# board.net
KiCad netlist of a schematic drawn in EAGLE
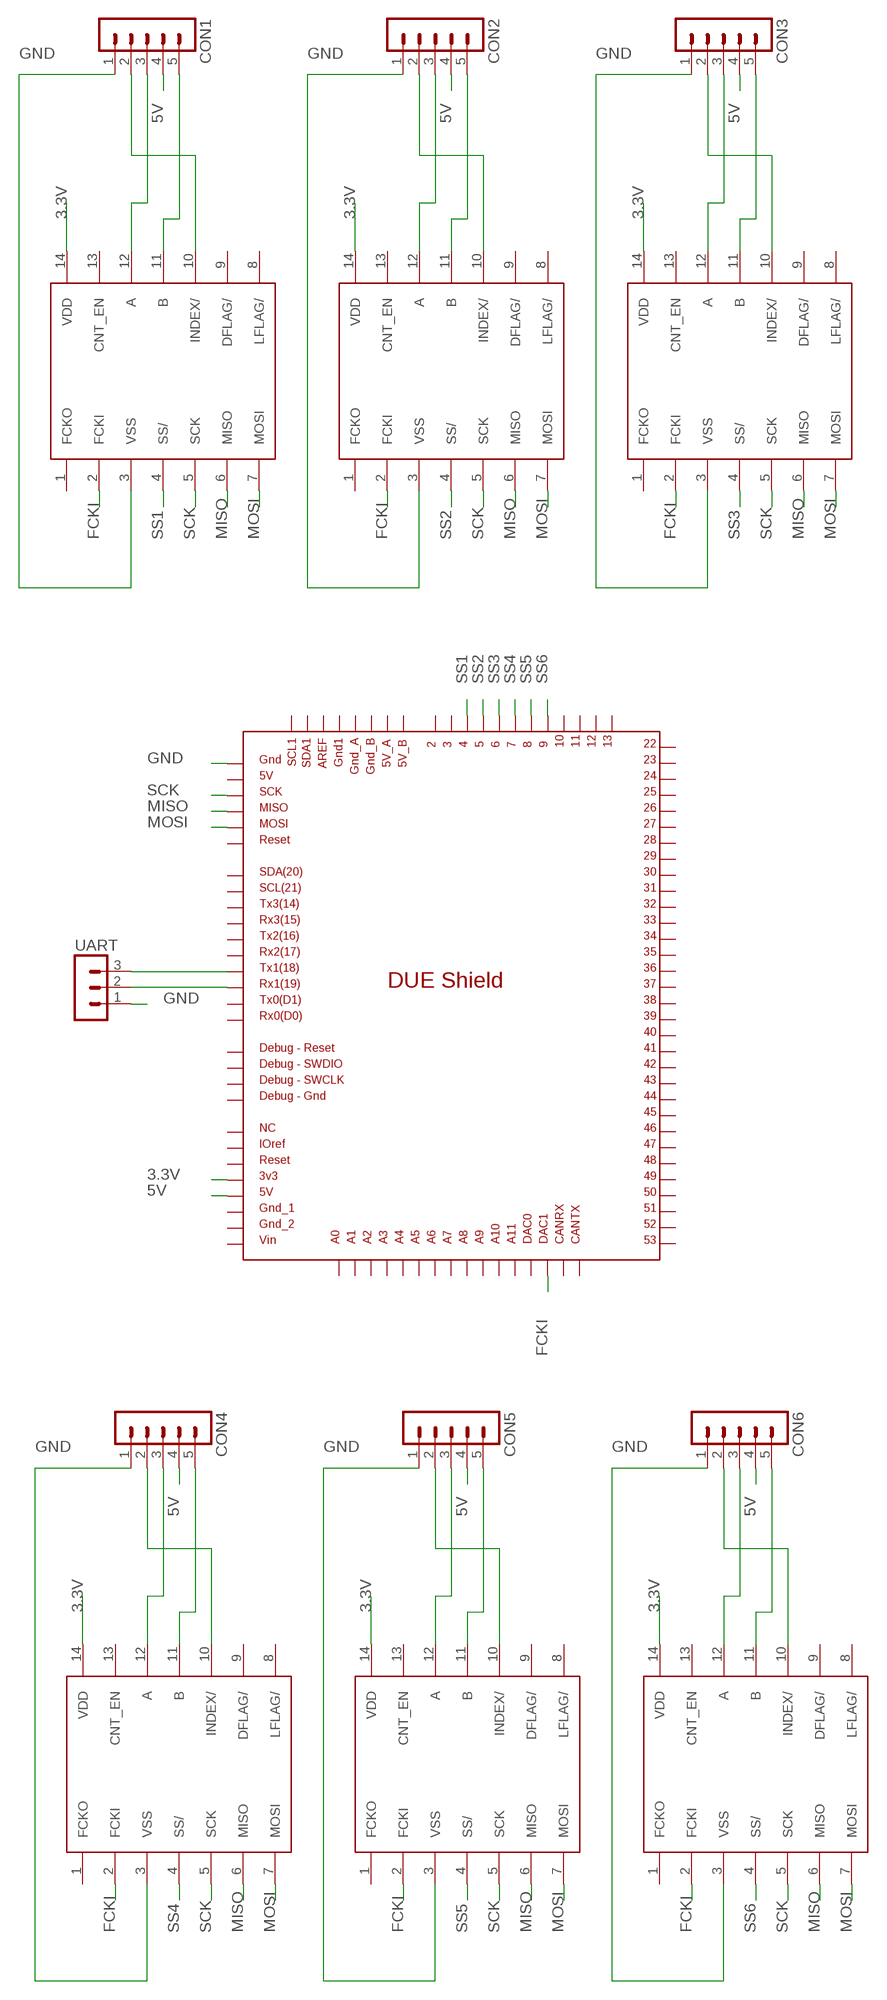
[diagram p0: schematic, sheet 1]

(export (version "E")
  (design (tool "Eeschema 10.0.6"))
  (components
    (comp (ref "CON1")
      (value "MA05-1")
      (footprint "eagle-import:MA05-1")
      (libsource (lib "eagle-import") (part "MA05-1"))
    )
    (comp (ref "CON2")
      (value "MA05-1")
      (footprint "eagle-import:MA05-1")
      (libsource (lib "eagle-import") (part "MA05-1"))
    )
    (comp (ref "CON3")
      (value "MA05-1")
      (footprint "eagle-import:MA05-1")
      (libsource (lib "eagle-import") (part "MA05-1"))
    )
    (comp (ref "CON4")
      (value "MA05-1")
      (footprint "eagle-import:MA05-1")
      (libsource (lib "eagle-import") (part "MA05-1"))
    )
    (comp (ref "CON5")
      (value "MA05-1")
      (footprint "eagle-import:MA05-1")
      (libsource (lib "eagle-import") (part "MA05-1"))
    )
    (comp (ref "CON6")
      (value "MA05-1")
      (footprint "eagle-import:MA05-1")
      (libsource (lib "eagle-import") (part "MA05-1"))
    )
    (comp (ref "IC1")
      (value "LFLS7366R")
      (footprint "eagle-import:SO14")
      (libsource (lib "eagle-import") (part "LFLS7366R"))
    )
    (comp (ref "IC2")
      (value "LFLS7366R")
      (footprint "eagle-import:SO14")
      (libsource (lib "eagle-import") (part "LFLS7366R"))
    )
    (comp (ref "IC3")
      (value "LFLS7366R")
      (footprint "eagle-import:SO14")
      (libsource (lib "eagle-import") (part "LFLS7366R"))
    )
    (comp (ref "IC4")
      (value "LFLS7366R")
      (footprint "eagle-import:SO14")
      (libsource (lib "eagle-import") (part "LFLS7366R"))
    )
    (comp (ref "IC5")
      (value "LFLS7366R")
      (footprint "eagle-import:SO14")
      (libsource (lib "eagle-import") (part "LFLS7366R"))
    )
    (comp (ref "IC6")
      (value "LFLS7366R")
      (footprint "eagle-import:SO14")
      (libsource (lib "eagle-import") (part "LFLS7366R"))
    )
    (comp (ref "U$7")
      (value "DUE(NORMAL)")
      (footprint "eagle-import:DUE(NORMAL)")
      (libsource (lib "eagle-import") (part "DUE(NORMAL)"))
    )
    (comp (ref "UART")
      (value "MA03-1")
      (footprint "eagle-import:MA03-1")
      (libsource (lib "eagle-import") (part "MA03-1"))
    )
  )
  (nets
    (net (code "1") (name "/3.3V") (class "Default")
      (node (ref "IC1") (pin "14") (pinfunction "VDD_14") (pintype "bidirectional"))
      (node (ref "IC2") (pin "14") (pinfunction "VDD_14") (pintype "bidirectional"))
      (node (ref "IC3") (pin "14") (pinfunction "VDD_14") (pintype "bidirectional"))
      (node (ref "IC4") (pin "14") (pinfunction "VDD_14") (pintype "bidirectional"))
      (node (ref "IC5") (pin "14") (pinfunction "VDD_14") (pintype "bidirectional"))
      (node (ref "IC6") (pin "14") (pinfunction "VDD_14") (pintype "bidirectional"))
      (node (ref "U$7") (pin "3V3") (pinfunction "3V3_3V3") (pintype "bidirectional"))
    )
    (net (code "2") (name "/5V") (class "Default")
      (node (ref "CON1") (pin "4") (pinfunction "4_4") (pintype "passive"))
      (node (ref "CON2") (pin "4") (pinfunction "4_4") (pintype "passive"))
      (node (ref "CON3") (pin "4") (pinfunction "4_4") (pintype "passive"))
      (node (ref "CON4") (pin "4") (pinfunction "4_4") (pintype "passive"))
      (node (ref "CON5") (pin "4") (pinfunction "4_4") (pintype "passive"))
      (node (ref "CON6") (pin "4") (pinfunction "4_4") (pintype "passive"))
      (node (ref "U$7") (pin "5V") (pinfunction "5V_5V") (pintype "bidirectional"))
    )
    (net (code "3") (name "/FCKI") (class "Default")
      (node (ref "IC1") (pin "2") (pinfunction "FCKI_2") (pintype "bidirectional"))
      (node (ref "IC2") (pin "2") (pinfunction "FCKI_2") (pintype "bidirectional"))
      (node (ref "IC3") (pin "2") (pinfunction "FCKI_2") (pintype "bidirectional"))
      (node (ref "IC4") (pin "2") (pinfunction "FCKI_2") (pintype "bidirectional"))
      (node (ref "IC5") (pin "2") (pinfunction "FCKI_2") (pintype "bidirectional"))
      (node (ref "IC6") (pin "2") (pinfunction "FCKI_2") (pintype "bidirectional"))
      (node (ref "U$7") (pin "DAC1") (pinfunction "DAC1_DAC1") (pintype "bidirectional"))
    )
    (net (code "4") (name "/GND") (class "Default")
      (node (ref "CON1") (pin "1") (pinfunction "1_1") (pintype "passive"))
      (node (ref "CON2") (pin "1") (pinfunction "1_1") (pintype "passive"))
      (node (ref "CON3") (pin "1") (pinfunction "1_1") (pintype "passive"))
      (node (ref "CON4") (pin "1") (pinfunction "1_1") (pintype "passive"))
      (node (ref "CON5") (pin "1") (pinfunction "1_1") (pintype "passive"))
      (node (ref "CON6") (pin "1") (pinfunction "1_1") (pintype "passive"))
      (node (ref "IC1") (pin "3") (pinfunction "VSS_3") (pintype "bidirectional"))
      (node (ref "IC2") (pin "3") (pinfunction "VSS_3") (pintype "bidirectional"))
      (node (ref "IC3") (pin "3") (pinfunction "VSS_3") (pintype "bidirectional"))
      (node (ref "IC4") (pin "3") (pinfunction "VSS_3") (pintype "bidirectional"))
      (node (ref "IC5") (pin "3") (pinfunction "VSS_3") (pintype "bidirectional"))
      (node (ref "IC6") (pin "3") (pinfunction "VSS_3") (pintype "bidirectional"))
      (node (ref "U$7") (pin "5V_ICSP") (pinfunction "5V_ICSP_5V_ICSP") (pintype "bidirectional"))
      (node (ref "UART") (pin "1") (pinfunction "1_1") (pintype "passive"))
    )
    (net (code "5") (name "/MISO") (class "Default")
      (node (ref "IC1") (pin "6") (pinfunction "MISO_6") (pintype "bidirectional"))
      (node (ref "IC2") (pin "6") (pinfunction "MISO_6") (pintype "bidirectional"))
      (node (ref "IC3") (pin "6") (pinfunction "MISO_6") (pintype "bidirectional"))
      (node (ref "IC4") (pin "6") (pinfunction "MISO_6") (pintype "bidirectional"))
      (node (ref "IC5") (pin "6") (pinfunction "MISO_6") (pintype "bidirectional"))
      (node (ref "IC6") (pin "6") (pinfunction "MISO_6") (pintype "bidirectional"))
      (node (ref "U$7") (pin "MISO_ICSP") (pinfunction "MISO_ICSP_MISO_ICSP") (pintype "bidirectional"))
    )
    (net (code "6") (name "/MOSI") (class "Default")
      (node (ref "IC1") (pin "7") (pinfunction "MOSI_7") (pintype "bidirectional"))
      (node (ref "IC2") (pin "7") (pinfunction "MOSI_7") (pintype "bidirectional"))
      (node (ref "IC3") (pin "7") (pinfunction "MOSI_7") (pintype "bidirectional"))
      (node (ref "IC4") (pin "7") (pinfunction "MOSI_7") (pintype "bidirectional"))
      (node (ref "IC5") (pin "7") (pinfunction "MOSI_7") (pintype "bidirectional"))
      (node (ref "IC6") (pin "7") (pinfunction "MOSI_7") (pintype "bidirectional"))
      (node (ref "U$7") (pin "MOSI_ICSP") (pinfunction "MOSI_ICSP_MOSI_ICSP") (pintype "bidirectional"))
    )
    (net (code "7") (name "/SCK") (class "Default")
      (node (ref "IC1") (pin "5") (pinfunction "SCK_5") (pintype "bidirectional"))
      (node (ref "IC2") (pin "5") (pinfunction "SCK_5") (pintype "bidirectional"))
      (node (ref "IC3") (pin "5") (pinfunction "SCK_5") (pintype "bidirectional"))
      (node (ref "IC4") (pin "5") (pinfunction "SCK_5") (pintype "bidirectional"))
      (node (ref "IC5") (pin "5") (pinfunction "SCK_5") (pintype "bidirectional"))
      (node (ref "IC6") (pin "5") (pinfunction "SCK_5") (pintype "bidirectional"))
      (node (ref "U$7") (pin "SCK_ICSP") (pinfunction "SCK_ICSP_SCK_ICSP") (pintype "bidirectional"))
    )
    (net (code "8") (name "/SS1") (class "Default")
      (node (ref "IC1") (pin "4") (pinfunction "SS/_4") (pintype "bidirectional"))
      (node (ref "U$7") (pin "4") (pinfunction "4_4") (pintype "bidirectional"))
    )
    (net (code "9") (name "/SS2") (class "Default")
      (node (ref "IC2") (pin "4") (pinfunction "SS/_4") (pintype "bidirectional"))
      (node (ref "U$7") (pin "5") (pinfunction "5_5") (pintype "bidirectional"))
    )
    (net (code "10") (name "/SS3") (class "Default")
      (node (ref "IC3") (pin "4") (pinfunction "SS/_4") (pintype "bidirectional"))
      (node (ref "U$7") (pin "6") (pinfunction "6_6") (pintype "bidirectional"))
    )
    (net (code "11") (name "/SS4") (class "Default")
      (node (ref "IC4") (pin "4") (pinfunction "SS/_4") (pintype "bidirectional"))
      (node (ref "U$7") (pin "7") (pinfunction "7_7") (pintype "bidirectional"))
    )
    (net (code "12") (name "/SS5") (class "Default")
      (node (ref "IC5") (pin "4") (pinfunction "SS/_4") (pintype "bidirectional"))
      (node (ref "U$7") (pin "8") (pinfunction "8_8") (pintype "bidirectional"))
    )
    (net (code "13") (name "/SS6") (class "Default")
      (node (ref "IC6") (pin "4") (pinfunction "SS/_4") (pintype "bidirectional"))
      (node (ref "U$7") (pin "9") (pinfunction "9_9") (pintype "bidirectional"))
    )
    (net (code "14") (name "Net-(IC1-A)") (class "Default")
      (node (ref "CON1") (pin "3") (pinfunction "3_3") (pintype "passive"))
      (node (ref "IC1") (pin "12") (pinfunction "A_12") (pintype "bidirectional"))
    )
    (net (code "15") (name "Net-(IC1-B)") (class "Default")
      (node (ref "CON1") (pin "5") (pinfunction "5_5") (pintype "passive"))
      (node (ref "IC1") (pin "11") (pinfunction "B_11") (pintype "bidirectional"))
    )
    (net (code "16") (name "Net-(IC1-INDEX{slash})") (class "Default")
      (node (ref "CON1") (pin "2") (pinfunction "2_2") (pintype "passive"))
      (node (ref "IC1") (pin "10") (pinfunction "INDEX/_10") (pintype "bidirectional"))
    )
    (net (code "17") (name "Net-(IC2-A)") (class "Default")
      (node (ref "CON2") (pin "3") (pinfunction "3_3") (pintype "passive"))
      (node (ref "IC2") (pin "12") (pinfunction "A_12") (pintype "bidirectional"))
    )
    (net (code "18") (name "Net-(IC2-B)") (class "Default")
      (node (ref "CON2") (pin "5") (pinfunction "5_5") (pintype "passive"))
      (node (ref "IC2") (pin "11") (pinfunction "B_11") (pintype "bidirectional"))
    )
    (net (code "19") (name "Net-(IC2-INDEX{slash})") (class "Default")
      (node (ref "CON2") (pin "2") (pinfunction "2_2") (pintype "passive"))
      (node (ref "IC2") (pin "10") (pinfunction "INDEX/_10") (pintype "bidirectional"))
    )
    (net (code "20") (name "Net-(IC3-A)") (class "Default")
      (node (ref "CON3") (pin "3") (pinfunction "3_3") (pintype "passive"))
      (node (ref "IC3") (pin "12") (pinfunction "A_12") (pintype "bidirectional"))
    )
    (net (code "21") (name "Net-(IC3-B)") (class "Default")
      (node (ref "CON3") (pin "5") (pinfunction "5_5") (pintype "passive"))
      (node (ref "IC3") (pin "11") (pinfunction "B_11") (pintype "bidirectional"))
    )
    (net (code "22") (name "Net-(IC3-INDEX{slash})") (class "Default")
      (node (ref "CON3") (pin "2") (pinfunction "2_2") (pintype "passive"))
      (node (ref "IC3") (pin "10") (pinfunction "INDEX/_10") (pintype "bidirectional"))
    )
    (net (code "23") (name "Net-(IC4-A)") (class "Default")
      (node (ref "CON4") (pin "3") (pinfunction "3_3") (pintype "passive"))
      (node (ref "IC4") (pin "12") (pinfunction "A_12") (pintype "bidirectional"))
    )
    (net (code "24") (name "Net-(IC4-B)") (class "Default")
      (node (ref "CON4") (pin "5") (pinfunction "5_5") (pintype "passive"))
      (node (ref "IC4") (pin "11") (pinfunction "B_11") (pintype "bidirectional"))
    )
    (net (code "25") (name "Net-(IC4-INDEX{slash})") (class "Default")
      (node (ref "CON4") (pin "2") (pinfunction "2_2") (pintype "passive"))
      (node (ref "IC4") (pin "10") (pinfunction "INDEX/_10") (pintype "bidirectional"))
    )
    (net (code "26") (name "Net-(IC5-A)") (class "Default")
      (node (ref "CON5") (pin "3") (pinfunction "3_3") (pintype "passive"))
      (node (ref "IC5") (pin "12") (pinfunction "A_12") (pintype "bidirectional"))
    )
    (net (code "27") (name "Net-(IC5-B)") (class "Default")
      (node (ref "CON5") (pin "5") (pinfunction "5_5") (pintype "passive"))
      (node (ref "IC5") (pin "11") (pinfunction "B_11") (pintype "bidirectional"))
    )
    (net (code "28") (name "Net-(IC5-INDEX{slash})") (class "Default")
      (node (ref "CON5") (pin "2") (pinfunction "2_2") (pintype "passive"))
      (node (ref "IC5") (pin "10") (pinfunction "INDEX/_10") (pintype "bidirectional"))
    )
    (net (code "29") (name "Net-(IC6-A)") (class "Default")
      (node (ref "CON6") (pin "3") (pinfunction "3_3") (pintype "passive"))
      (node (ref "IC6") (pin "12") (pinfunction "A_12") (pintype "bidirectional"))
    )
    (net (code "30") (name "Net-(IC6-B)") (class "Default")
      (node (ref "CON6") (pin "5") (pinfunction "5_5") (pintype "passive"))
      (node (ref "IC6") (pin "11") (pinfunction "B_11") (pintype "bidirectional"))
    )
    (net (code "31") (name "Net-(IC6-INDEX{slash})") (class "Default")
      (node (ref "CON6") (pin "2") (pinfunction "2_2") (pintype "passive"))
      (node (ref "IC6") (pin "10") (pinfunction "INDEX/_10") (pintype "bidirectional"))
    )
    (net (code "32") (name "Net-(U$7-PadRX1)") (class "Default")
      (node (ref "U$7") (pin "RX1") (pinfunction "RX1_RX1") (pintype "bidirectional"))
      (node (ref "UART") (pin "2") (pinfunction "2_2") (pintype "passive"))
    )
    (net (code "33") (name "Net-(U$7-PadTX1)") (class "Default")
      (node (ref "U$7") (pin "TX1") (pinfunction "TX1_TX1") (pintype "bidirectional"))
      (node (ref "UART") (pin "3") (pinfunction "3_3") (pintype "passive"))
    )
    (net (code "34") (name "unconnected-(IC1-CNT_EN-Pad13)") (class "Default")
      (node (ref "IC1") (pin "13") (pinfunction "CNT_EN_13") (pintype "bidirectional"))
    )
    (net (code "35") (name "unconnected-(IC1-DFLAG{slash}-Pad9)") (class "Default")
      (node (ref "IC1") (pin "9") (pinfunction "DFLAG/_9") (pintype "bidirectional"))
    )
    (net (code "36") (name "unconnected-(IC1-FCKO-Pad1)") (class "Default")
      (node (ref "IC1") (pin "1") (pinfunction "FCKO_1") (pintype "bidirectional"))
    )
    (net (code "37") (name "unconnected-(IC1-LFLAG{slash}-Pad8)") (class "Default")
      (node (ref "IC1") (pin "8") (pinfunction "LFLAG/_8") (pintype "bidirectional"))
    )
    (net (code "38") (name "unconnected-(IC2-CNT_EN-Pad13)") (class "Default")
      (node (ref "IC2") (pin "13") (pinfunction "CNT_EN_13") (pintype "bidirectional"))
    )
    (net (code "39") (name "unconnected-(IC2-DFLAG{slash}-Pad9)") (class "Default")
      (node (ref "IC2") (pin "9") (pinfunction "DFLAG/_9") (pintype "bidirectional"))
    )
    (net (code "40") (name "unconnected-(IC2-FCKO-Pad1)") (class "Default")
      (node (ref "IC2") (pin "1") (pinfunction "FCKO_1") (pintype "bidirectional"))
    )
    (net (code "41") (name "unconnected-(IC2-LFLAG{slash}-Pad8)") (class "Default")
      (node (ref "IC2") (pin "8") (pinfunction "LFLAG/_8") (pintype "bidirectional"))
    )
    (net (code "42") (name "unconnected-(IC3-CNT_EN-Pad13)") (class "Default")
      (node (ref "IC3") (pin "13") (pinfunction "CNT_EN_13") (pintype "bidirectional"))
    )
    (net (code "43") (name "unconnected-(IC3-DFLAG{slash}-Pad9)") (class "Default")
      (node (ref "IC3") (pin "9") (pinfunction "DFLAG/_9") (pintype "bidirectional"))
    )
    (net (code "44") (name "unconnected-(IC3-FCKO-Pad1)") (class "Default")
      (node (ref "IC3") (pin "1") (pinfunction "FCKO_1") (pintype "bidirectional"))
    )
    (net (code "45") (name "unconnected-(IC3-LFLAG{slash}-Pad8)") (class "Default")
      (node (ref "IC3") (pin "8") (pinfunction "LFLAG/_8") (pintype "bidirectional"))
    )
    (net (code "46") (name "unconnected-(IC4-CNT_EN-Pad13)") (class "Default")
      (node (ref "IC4") (pin "13") (pinfunction "CNT_EN_13") (pintype "bidirectional"))
    )
    (net (code "47") (name "unconnected-(IC4-DFLAG{slash}-Pad9)") (class "Default")
      (node (ref "IC4") (pin "9") (pinfunction "DFLAG/_9") (pintype "bidirectional"))
    )
    (net (code "48") (name "unconnected-(IC4-FCKO-Pad1)") (class "Default")
      (node (ref "IC4") (pin "1") (pinfunction "FCKO_1") (pintype "bidirectional"))
    )
    (net (code "49") (name "unconnected-(IC4-LFLAG{slash}-Pad8)") (class "Default")
      (node (ref "IC4") (pin "8") (pinfunction "LFLAG/_8") (pintype "bidirectional"))
    )
    (net (code "50") (name "unconnected-(IC5-CNT_EN-Pad13)") (class "Default")
      (node (ref "IC5") (pin "13") (pinfunction "CNT_EN_13") (pintype "bidirectional"))
    )
    (net (code "51") (name "unconnected-(IC5-DFLAG{slash}-Pad9)") (class "Default")
      (node (ref "IC5") (pin "9") (pinfunction "DFLAG/_9") (pintype "bidirectional"))
    )
    (net (code "52") (name "unconnected-(IC5-FCKO-Pad1)") (class "Default")
      (node (ref "IC5") (pin "1") (pinfunction "FCKO_1") (pintype "bidirectional"))
    )
    (net (code "53") (name "unconnected-(IC5-LFLAG{slash}-Pad8)") (class "Default")
      (node (ref "IC5") (pin "8") (pinfunction "LFLAG/_8") (pintype "bidirectional"))
    )
    (net (code "54") (name "unconnected-(IC6-CNT_EN-Pad13)") (class "Default")
      (node (ref "IC6") (pin "13") (pinfunction "CNT_EN_13") (pintype "bidirectional"))
    )
    (net (code "55") (name "unconnected-(IC6-DFLAG{slash}-Pad9)") (class "Default")
      (node (ref "IC6") (pin "9") (pinfunction "DFLAG/_9") (pintype "bidirectional"))
    )
    (net (code "56") (name "unconnected-(IC6-FCKO-Pad1)") (class "Default")
      (node (ref "IC6") (pin "1") (pinfunction "FCKO_1") (pintype "bidirectional"))
    )
    (net (code "57") (name "unconnected-(IC6-LFLAG{slash}-Pad8)") (class "Default")
      (node (ref "IC6") (pin "8") (pinfunction "LFLAG/_8") (pintype "bidirectional"))
    )
    (net (code "58") (name "unconnected-(U$7-Pad2)") (class "Default")
      (node (ref "U$7") (pin "2") (pinfunction "2_2") (pintype "bidirectional"))
    )
    (net (code "59") (name "unconnected-(U$7-Pad3)") (class "Default")
      (node (ref "U$7") (pin "3") (pinfunction "3_3") (pintype "bidirectional"))
    )
    (net (code "60") (name "unconnected-(U$7-Pad5V_A)") (class "Default")
      (node (ref "U$7") (pin "5V_A") (pinfunction "5V_A_5V_A") (pintype "bidirectional"))
    )
    (net (code "61") (name "unconnected-(U$7-Pad5V_B)") (class "Default")
      (node (ref "U$7") (pin "5V_B") (pinfunction "5V_B_5V_B") (pintype "bidirectional"))
    )
    (net (code "62") (name "unconnected-(U$7-Pad10)") (class "Default")
      (node (ref "U$7") (pin "10") (pinfunction "10_10") (pintype "bidirectional"))
    )
    (net (code "63") (name "unconnected-(U$7-Pad11)") (class "Default")
      (node (ref "U$7") (pin "11") (pinfunction "11_11") (pintype "bidirectional"))
    )
    (net (code "64") (name "unconnected-(U$7-Pad12)") (class "Default")
      (node (ref "U$7") (pin "12") (pinfunction "12_12") (pintype "bidirectional"))
    )
    (net (code "65") (name "unconnected-(U$7-Pad13)") (class "Default")
      (node (ref "U$7") (pin "13") (pinfunction "13_13") (pintype "bidirectional"))
    )
    (net (code "66") (name "unconnected-(U$7-Pad22)") (class "Default")
      (node (ref "U$7") (pin "22") (pinfunction "22_22") (pintype "bidirectional"))
    )
    (net (code "67") (name "unconnected-(U$7-Pad23)") (class "Default")
      (node (ref "U$7") (pin "23") (pinfunction "23_23") (pintype "bidirectional"))
    )
    (net (code "68") (name "unconnected-(U$7-Pad24)") (class "Default")
      (node (ref "U$7") (pin "24") (pinfunction "24_24") (pintype "bidirectional"))
    )
    (net (code "69") (name "unconnected-(U$7-Pad25)") (class "Default")
      (node (ref "U$7") (pin "25") (pinfunction "25_25") (pintype "bidirectional"))
    )
    (net (code "70") (name "unconnected-(U$7-Pad26)") (class "Default")
      (node (ref "U$7") (pin "26") (pinfunction "26_26") (pintype "bidirectional"))
    )
    (net (code "71") (name "unconnected-(U$7-Pad27)") (class "Default")
      (node (ref "U$7") (pin "27") (pinfunction "27_27") (pintype "bidirectional"))
    )
    (net (code "72") (name "unconnected-(U$7-Pad28)") (class "Default")
      (node (ref "U$7") (pin "28") (pinfunction "28_28") (pintype "bidirectional"))
    )
    (net (code "73") (name "unconnected-(U$7-Pad29)") (class "Default")
      (node (ref "U$7") (pin "29") (pinfunction "29_29") (pintype "bidirectional"))
    )
    (net (code "74") (name "unconnected-(U$7-Pad30)") (class "Default")
      (node (ref "U$7") (pin "30") (pinfunction "30_30") (pintype "bidirectional"))
    )
    (net (code "75") (name "unconnected-(U$7-Pad31)") (class "Default")
      (node (ref "U$7") (pin "31") (pinfunction "31_31") (pintype "bidirectional"))
    )
    (net (code "76") (name "unconnected-(U$7-Pad32)") (class "Default")
      (node (ref "U$7") (pin "32") (pinfunction "32_32") (pintype "bidirectional"))
    )
    (net (code "77") (name "unconnected-(U$7-Pad33)") (class "Default")
      (node (ref "U$7") (pin "33") (pinfunction "33_33") (pintype "bidirectional"))
    )
    (net (code "78") (name "unconnected-(U$7-Pad34)") (class "Default")
      (node (ref "U$7") (pin "34") (pinfunction "34_34") (pintype "bidirectional"))
    )
    (net (code "79") (name "unconnected-(U$7-Pad35)") (class "Default")
      (node (ref "U$7") (pin "35") (pinfunction "35_35") (pintype "bidirectional"))
    )
    (net (code "80") (name "unconnected-(U$7-Pad36)") (class "Default")
      (node (ref "U$7") (pin "36") (pinfunction "36_36") (pintype "bidirectional"))
    )
    (net (code "81") (name "unconnected-(U$7-Pad37)") (class "Default")
      (node (ref "U$7") (pin "37") (pinfunction "37_37") (pintype "bidirectional"))
    )
    (net (code "82") (name "unconnected-(U$7-Pad38)") (class "Default")
      (node (ref "U$7") (pin "38") (pinfunction "38_38") (pintype "bidirectional"))
    )
    (net (code "83") (name "unconnected-(U$7-Pad39)") (class "Default")
      (node (ref "U$7") (pin "39") (pinfunction "39_39") (pintype "bidirectional"))
    )
    (net (code "84") (name "unconnected-(U$7-Pad40)") (class "Default")
      (node (ref "U$7") (pin "40") (pinfunction "40_40") (pintype "bidirectional"))
    )
    (net (code "85") (name "unconnected-(U$7-Pad41)") (class "Default")
      (node (ref "U$7") (pin "41") (pinfunction "41_41") (pintype "bidirectional"))
    )
    (net (code "86") (name "unconnected-(U$7-Pad42)") (class "Default")
      (node (ref "U$7") (pin "42") (pinfunction "42_42") (pintype "bidirectional"))
    )
    (net (code "87") (name "unconnected-(U$7-Pad43)") (class "Default")
      (node (ref "U$7") (pin "43") (pinfunction "43_43") (pintype "bidirectional"))
    )
    (net (code "88") (name "unconnected-(U$7-Pad44)") (class "Default")
      (node (ref "U$7") (pin "44") (pinfunction "44_44") (pintype "bidirectional"))
    )
    (net (code "89") (name "unconnected-(U$7-Pad45)") (class "Default")
      (node (ref "U$7") (pin "45") (pinfunction "45_45") (pintype "bidirectional"))
    )
    (net (code "90") (name "unconnected-(U$7-Pad46)") (class "Default")
      (node (ref "U$7") (pin "46") (pinfunction "46_46") (pintype "bidirectional"))
    )
    (net (code "91") (name "unconnected-(U$7-Pad47)") (class "Default")
      (node (ref "U$7") (pin "47") (pinfunction "47_47") (pintype "bidirectional"))
    )
    (net (code "92") (name "unconnected-(U$7-Pad48)") (class "Default")
      (node (ref "U$7") (pin "48") (pinfunction "48_48") (pintype "bidirectional"))
    )
    (net (code "93") (name "unconnected-(U$7-Pad49)") (class "Default")
      (node (ref "U$7") (pin "49") (pinfunction "49_49") (pintype "bidirectional"))
    )
    (net (code "94") (name "unconnected-(U$7-Pad50)") (class "Default")
      (node (ref "U$7") (pin "50") (pinfunction "50_50") (pintype "bidirectional"))
    )
    (net (code "95") (name "unconnected-(U$7-Pad51)") (class "Default")
      (node (ref "U$7") (pin "51") (pinfunction "51_51") (pintype "bidirectional"))
    )
    (net (code "96") (name "unconnected-(U$7-Pad52)") (class "Default")
      (node (ref "U$7") (pin "52") (pinfunction "52_52") (pintype "bidirectional"))
    )
    (net (code "97") (name "unconnected-(U$7-Pad53)") (class "Default")
      (node (ref "U$7") (pin "53") (pinfunction "53_53") (pintype "bidirectional"))
    )
    (net (code "98") (name "unconnected-(U$7-PadA0)") (class "Default")
      (node (ref "U$7") (pin "A0") (pinfunction "A0_A0") (pintype "bidirectional"))
    )
    (net (code "99") (name "unconnected-(U$7-PadA1)") (class "Default")
      (node (ref "U$7") (pin "A1") (pinfunction "A1_A1") (pintype "bidirectional"))
    )
    (net (code "100") (name "unconnected-(U$7-PadA2)") (class "Default")
      (node (ref "U$7") (pin "A2") (pinfunction "A2_A2") (pintype "bidirectional"))
    )
    (net (code "101") (name "unconnected-(U$7-PadA3)") (class "Default")
      (node (ref "U$7") (pin "A3") (pinfunction "A3_A3") (pintype "bidirectional"))
    )
    (net (code "102") (name "unconnected-(U$7-PadA4)") (class "Default")
      (node (ref "U$7") (pin "A4") (pinfunction "A4_A4") (pintype "bidirectional"))
    )
    (net (code "103") (name "unconnected-(U$7-PadA5)") (class "Default")
      (node (ref "U$7") (pin "A5") (pinfunction "A5_A5") (pintype "bidirectional"))
    )
    (net (code "104") (name "unconnected-(U$7-PadA6)") (class "Default")
      (node (ref "U$7") (pin "A6") (pinfunction "A6_A6") (pintype "bidirectional"))
    )
    (net (code "105") (name "unconnected-(U$7-PadA7)") (class "Default")
      (node (ref "U$7") (pin "A7") (pinfunction "A7_A7") (pintype "bidirectional"))
    )
    (net (code "106") (name "unconnected-(U$7-PadA8)") (class "Default")
      (node (ref "U$7") (pin "A8") (pinfunction "A8_A8") (pintype "bidirectional"))
    )
    (net (code "107") (name "unconnected-(U$7-PadA9)") (class "Default")
      (node (ref "U$7") (pin "A9") (pinfunction "A9_A9") (pintype "bidirectional"))
    )
    (net (code "108") (name "unconnected-(U$7-PadA10)") (class "Default")
      (node (ref "U$7") (pin "A10") (pinfunction "A10_A10") (pintype "bidirectional"))
    )
    (net (code "109") (name "unconnected-(U$7-PadA11)") (class "Default")
      (node (ref "U$7") (pin "A11") (pinfunction "A11_A11") (pintype "bidirectional"))
    )
    (net (code "110") (name "unconnected-(U$7-PadAREF)") (class "Default")
      (node (ref "U$7") (pin "AREF") (pinfunction "AREF_AREF") (pintype "bidirectional"))
    )
    (net (code "111") (name "unconnected-(U$7-PadCANRX)") (class "Default")
      (node (ref "U$7") (pin "CANRX") (pinfunction "CANRX_CANRX") (pintype "bidirectional"))
    )
    (net (code "112") (name "unconnected-(U$7-PadCANTX)") (class "Default")
      (node (ref "U$7") (pin "CANTX") (pinfunction "CANTX_CANTX") (pintype "bidirectional"))
    )
    (net (code "113") (name "unconnected-(U$7-PadDAC0)") (class "Default")
      (node (ref "U$7") (pin "DAC0") (pinfunction "DAC0_DAC0") (pintype "bidirectional"))
    )
    (net (code "114") (name "unconnected-(U$7-PadGND1)") (class "Default")
      (node (ref "U$7") (pin "GND1") (pinfunction "GND1_GND1") (pintype "bidirectional"))
    )
    (net (code "115") (name "unconnected-(U$7-PadGND_1)") (class "Default")
      (node (ref "U$7") (pin "GND_1") (pinfunction "GND_1_GND_1") (pintype "bidirectional"))
    )
    (net (code "116") (name "unconnected-(U$7-PadGND_2)") (class "Default")
      (node (ref "U$7") (pin "GND_2") (pinfunction "GND_2_GND_2") (pintype "bidirectional"))
    )
    (net (code "117") (name "unconnected-(U$7-PadGND_A)") (class "Default")
      (node (ref "U$7") (pin "GND_A") (pinfunction "GND_A_GND_A") (pintype "bidirectional"))
    )
    (net (code "118") (name "unconnected-(U$7-PadGND_B)") (class "Default")
      (node (ref "U$7") (pin "GND_B") (pinfunction "GND_B_GND_B") (pintype "bidirectional"))
    )
    (net (code "119") (name "unconnected-(U$7-PadGND_DEBUG)") (class "Default")
      (node (ref "U$7") (pin "GND_DEBUG") (pinfunction "GND_DEBUG_GND_DEBUG") (pintype "bidirectional"))
    )
    (net (code "120") (name "unconnected-(U$7-PadGND_ICSP)") (class "Default")
      (node (ref "U$7") (pin "GND_ICSP") (pinfunction "GND_ICSP_GND_ICSP") (pintype "bidirectional"))
    )
    (net (code "121") (name "unconnected-(U$7-PadIOREF)") (class "Default")
      (node (ref "U$7") (pin "IOREF") (pinfunction "IOREF_IOREF") (pintype "bidirectional"))
    )
    (net (code "122") (name "unconnected-(U$7-PadNC)") (class "Default")
      (node (ref "U$7") (pin "NC") (pinfunction "NC_NC") (pintype "bidirectional"))
    )
    (net (code "123") (name "unconnected-(U$7-PadRESET)") (class "Default")
      (node (ref "U$7") (pin "RESET") (pinfunction "RESET_RESET") (pintype "bidirectional"))
    )
    (net (code "124") (name "unconnected-(U$7-PadRESET_DEBUG)") (class "Default")
      (node (ref "U$7") (pin "RESET_DEBUG") (pinfunction "RESET_DEBUG_RESET_DEBUG") (pintype "bidirectional"))
    )
    (net (code "125") (name "unconnected-(U$7-PadRESET_ICSP)") (class "Default")
      (node (ref "U$7") (pin "RESET_ICSP") (pinfunction "RESET_ICSP_RESET_ICSP") (pintype "bidirectional"))
    )
    (net (code "126") (name "unconnected-(U$7-PadRX0)") (class "Default")
      (node (ref "U$7") (pin "RX0") (pinfunction "RX0_RX0") (pintype "bidirectional"))
    )
    (net (code "127") (name "unconnected-(U$7-PadRX2)") (class "Default")
      (node (ref "U$7") (pin "RX2") (pinfunction "RX2_RX2") (pintype "bidirectional"))
    )
    (net (code "128") (name "unconnected-(U$7-PadRX3)") (class "Default")
      (node (ref "U$7") (pin "RX3") (pinfunction "RX3_RX3") (pintype "bidirectional"))
    )
    (net (code "129") (name "unconnected-(U$7-PadSCL)") (class "Default")
      (node (ref "U$7") (pin "SCL") (pinfunction "SCL_SCL") (pintype "bidirectional"))
    )
    (net (code "130") (name "unconnected-(U$7-PadSCL1)") (class "Default")
      (node (ref "U$7") (pin "SCL1") (pinfunction "SCL1_SCL1") (pintype "bidirectional"))
    )
    (net (code "131") (name "unconnected-(U$7-PadSDA)") (class "Default")
      (node (ref "U$7") (pin "SDA") (pinfunction "SDA_SDA") (pintype "bidirectional"))
    )
    (net (code "132") (name "unconnected-(U$7-PadSDA1)") (class "Default")
      (node (ref "U$7") (pin "SDA1") (pinfunction "SDA1_SDA1") (pintype "bidirectional"))
    )
    (net (code "133") (name "unconnected-(U$7-PadSWCLK_DEBUG)") (class "Default")
      (node (ref "U$7") (pin "SWCLK_DEBUG") (pinfunction "SWCLK_DEBUG_SWCLK_DEBUG") (pintype "bidirectional"))
    )
    (net (code "134") (name "unconnected-(U$7-PadSWDIO_DEBUG)") (class "Default")
      (node (ref "U$7") (pin "SWDIO_DEBUG") (pinfunction "SWDIO_DEBUG_SWDIO_DEBUG") (pintype "bidirectional"))
    )
    (net (code "135") (name "unconnected-(U$7-PadTX0)") (class "Default")
      (node (ref "U$7") (pin "TX0") (pinfunction "TX0_TX0") (pintype "bidirectional"))
    )
    (net (code "136") (name "unconnected-(U$7-PadTX2)") (class "Default")
      (node (ref "U$7") (pin "TX2") (pinfunction "TX2_TX2") (pintype "bidirectional"))
    )
    (net (code "137") (name "unconnected-(U$7-PadTX3)") (class "Default")
      (node (ref "U$7") (pin "TX3") (pinfunction "TX3_TX3") (pintype "bidirectional"))
    )
    (net (code "138") (name "unconnected-(U$7-PadVIN)") (class "Default")
      (node (ref "U$7") (pin "VIN") (pinfunction "VIN_VIN") (pintype "bidirectional"))
    )
  )
)
